# VHFA_RF_detector.net
KiCad netlist of a schematic drawn in Altium Designer
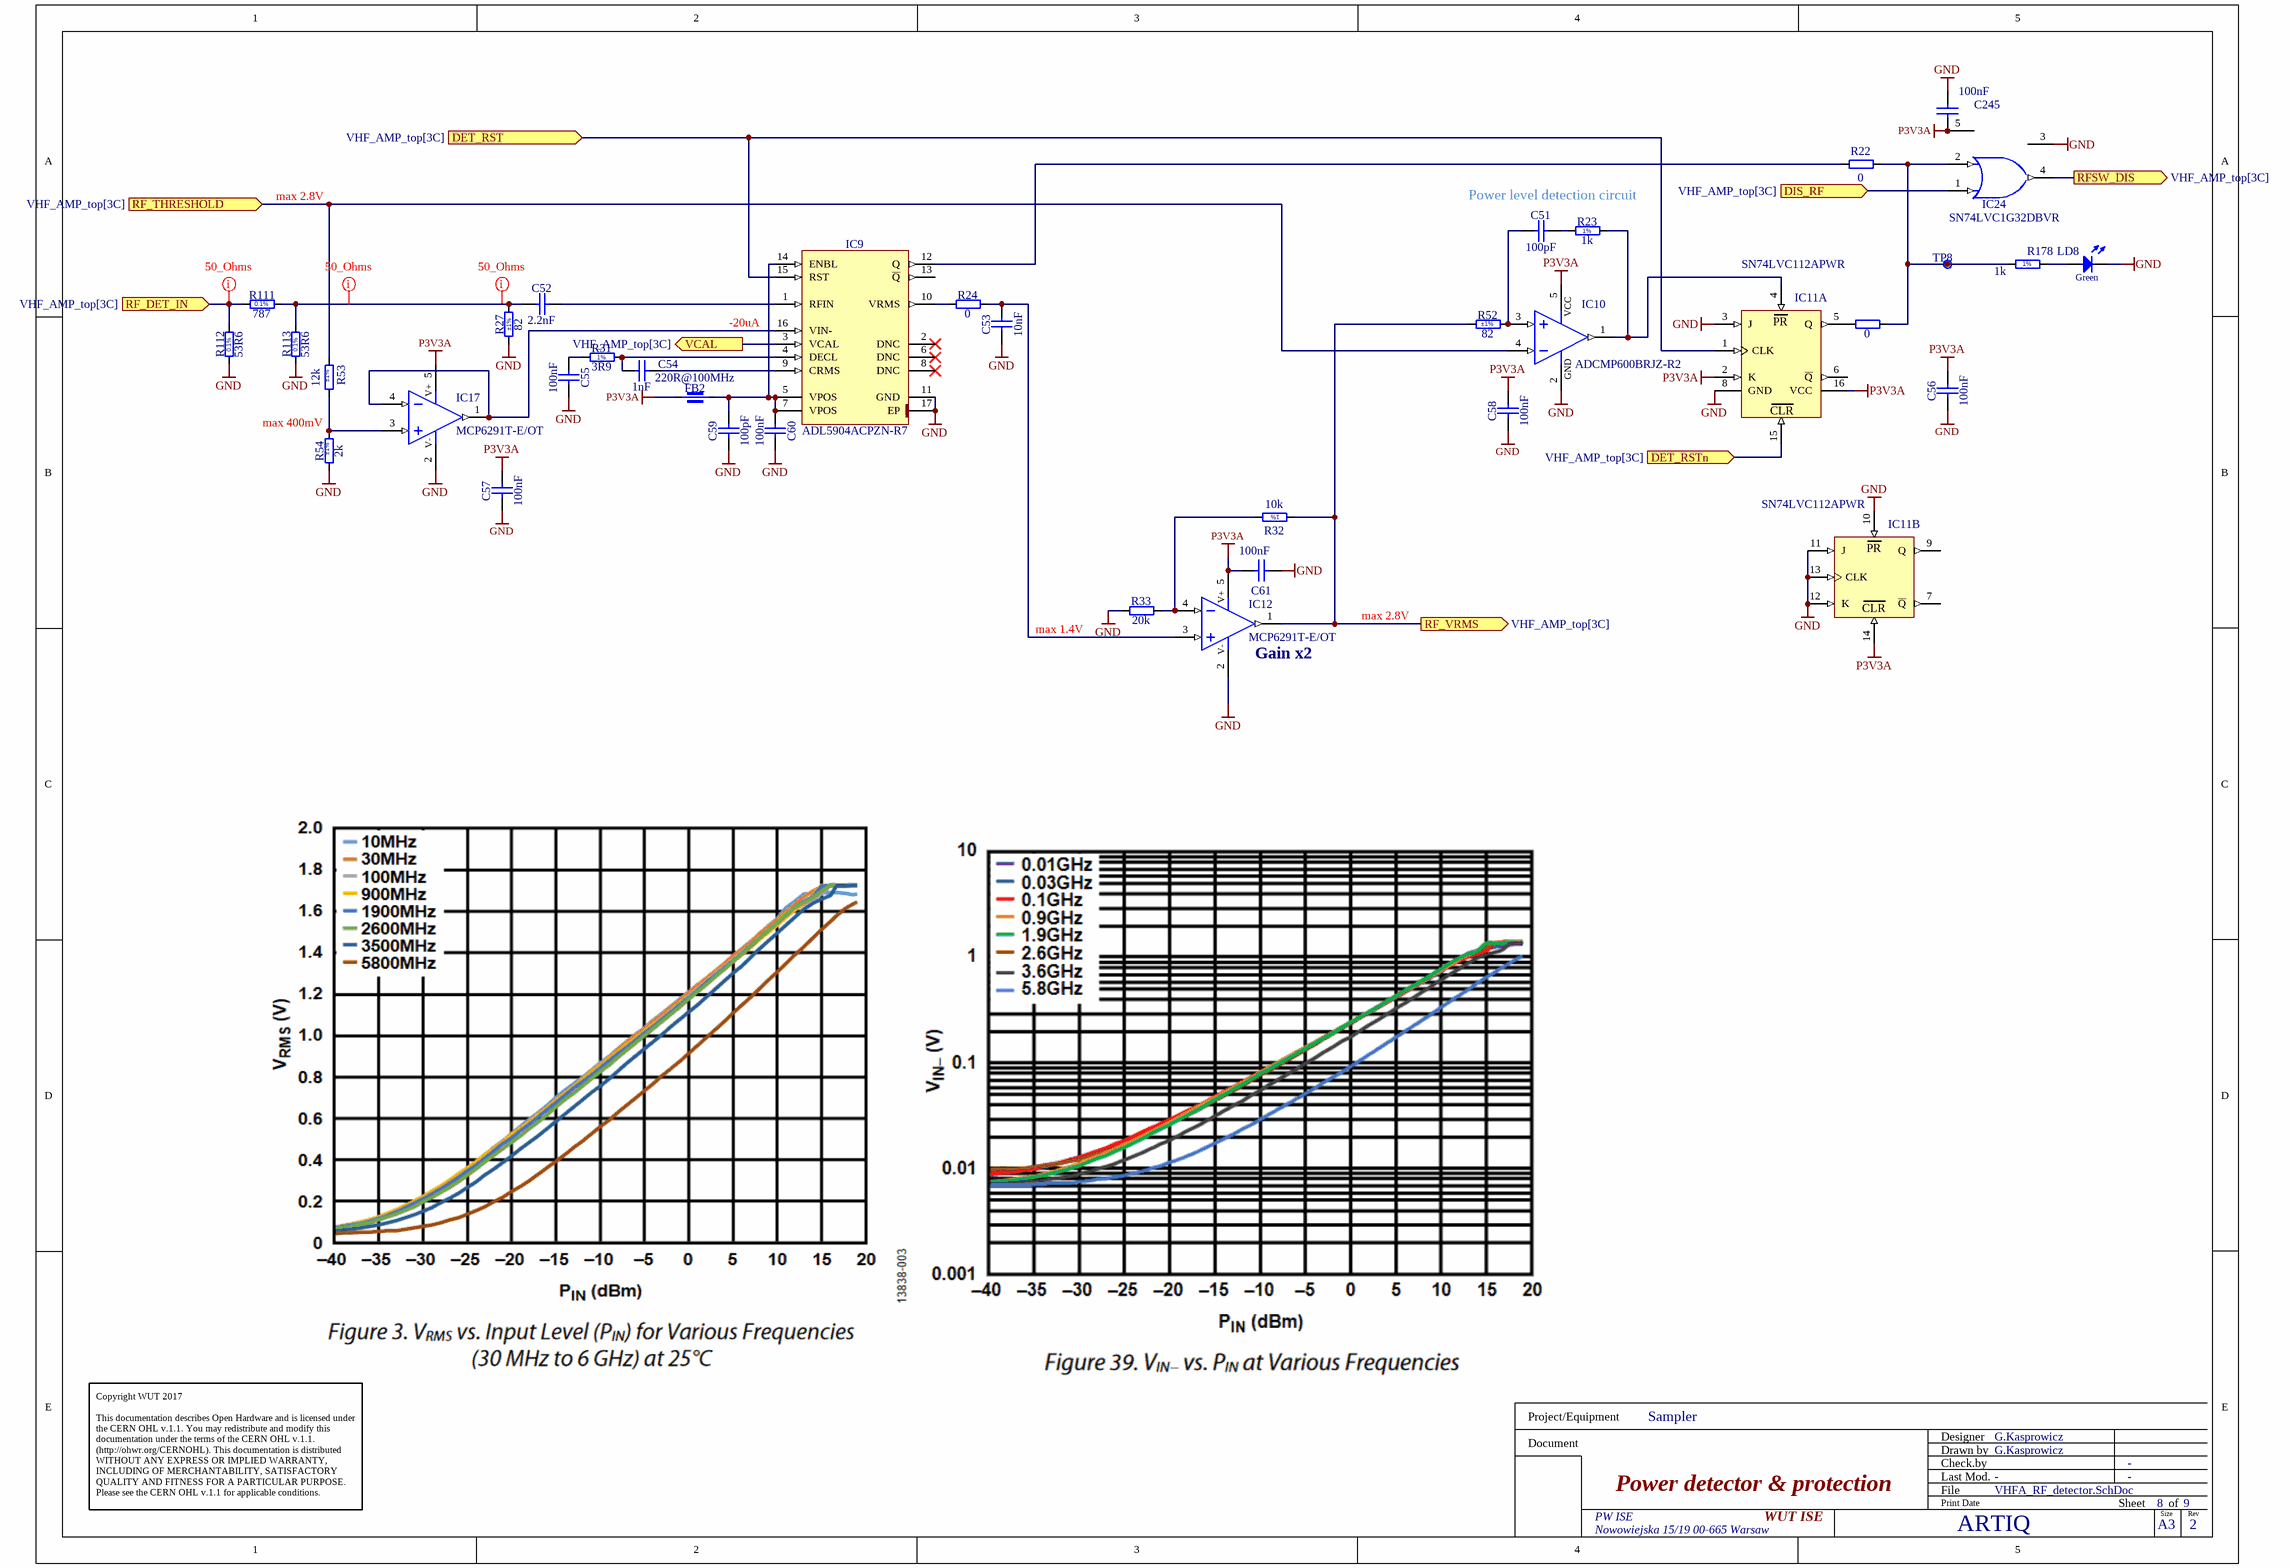
[diagram p0: VHFA_RF_detector.SchDoc]

(export (version "E")
  (design (tool "Eeschema 10.0.6"))
  (components
    (comp (ref "C51")
      (value "100pF")
      (footprint "CAPC1005X55N")
      (description "Non-polarised capacitor")
      (fields
        (field (name "PART NUMBER") "CC0402_100PF_50V_5%_C0G")
        (field (name "VOLTAGE") "50V")
        (field (name "AUTHOR") "CERN DEM JLC")
      )
      (libsource (lib "Capacitors") (part "Capacitor - non polarized"))
    )
    (comp (ref "C52")
      (value "2.2nF")
      (footprint "CAPC1608X87N")
      (description "Non-polarised capacitor")
      (fields
        (field (name "MANUFACTURER") "GENERIC")
        (field (name "MANUFACTURER PART NUMBER") "CC0603_2.2NF_50V_5%_C0G")
        (field (name "AUTHOR") "CERN DEM JMW")
      )
      (libsource (lib "Capacitors") (part "Capacitor - non polarized"))
    )
    (comp (ref "C53")
      (value "10nF")
      (footprint "CAPC1005X55N")
      (description "Non-polarised capacitor")
      (fields
        (field (name "MANUFACTURER") "GENERIC")
        (field (name "MANUFACTURER PART NUMBER") "CC0402_10NF_25V_10%_X7R")
        (field (name "AUTHOR") "CERN DEM JLC")
      )
      (libsource (lib "Capacitors") (part "Capacitor - non polarized"))
    )
    (comp (ref "C54")
      (value "1nF")
      (footprint "CAPC1005X55N")
      (description "Non-polarised capacitor")
      (fields
        (field (name "PART NUMBER") "CC0402_1NF_50V_10%_X7R")
        (field (name "VOLTAGE") "50V")
        (field (name "AUTHOR") "CERN DEM JLC")
      )
      (libsource (lib "Capacitors") (part "Capacitor - non polarized"))
    )
    (comp (ref "C55")
      (value "100nF")
      (footprint "CAPC1005X55N")
      (description "Non-polarised capacitor")
      (fields
        (field (name "MANUFACTURER") "GENERIC")
        (field (name "MANUFACTURER PART NUMBER") "CC0402_100NF_50V_10%_X7R")
        (field (name "AUTHOR") "CERN DEM MR")
      )
      (libsource (lib "Capacitors") (part "Capacitor - non polarized"))
    )
    (comp (ref "C56")
      (value "100nF")
      (footprint "CAPC1005X55N")
      (description "Non-polarised capacitor")
      (fields
        (field (name "PART NUMBER") "CC0402_100NF_16V_10%_X5R")
        (field (name "VOLTAGE") "16V")
        (field (name "AUTHOR") "CERN DEM JLC")
      )
      (libsource (lib "Capacitors") (part "Capacitor - non polarized"))
    )
    (comp (ref "C57")
      (value "100nF")
      (footprint "CAPC1005X55N")
      (description "Non-polarised capacitor")
      (fields
        (field (name "PART NUMBER") "CC0402_100NF_16V_10%_X5R")
        (field (name "VOLTAGE") "16V")
        (field (name "AUTHOR") "CERN DEM JLC")
      )
      (libsource (lib "Capacitors") (part "Capacitor - non polarized"))
    )
    (comp (ref "C58")
      (value "100nF")
      (footprint "CAPC1005X55N")
      (description "Non-polarised capacitor")
      (fields
        (field (name "PART NUMBER") "CC0402_100NF_16V_10%_X5R")
        (field (name "VOLTAGE") "16V")
        (field (name "AUTHOR") "CERN DEM JLC")
      )
      (libsource (lib "Capacitors") (part "Capacitor - non polarized"))
    )
    (comp (ref "C59")
      (value "100pF")
      (footprint "CAPC1005X55N")
      (description "Non-polarised capacitor")
      (fields
        (field (name "PART NUMBER") "CC0402_100PF_50V_5%_C0G")
        (field (name "VOLTAGE") "50V")
        (field (name "AUTHOR") "CERN DEM JLC")
      )
      (libsource (lib "Capacitors") (part "Capacitor - non polarized"))
    )
    (comp (ref "C60")
      (value "100nF")
      (footprint "CAPC1005X55N")
      (description "Non-polarised capacitor")
      (fields
        (field (name "MANUFACTURER") "GENERIC")
        (field (name "MANUFACTURER PART NUMBER") "CC0402_100NF_50V_10%_X7R")
        (field (name "AUTHOR") "CERN DEM MR")
      )
      (libsource (lib "Capacitors") (part "Capacitor - non polarized"))
    )
    (comp (ref "C61")
      (value "100nF")
      (footprint "CAPC1005X55N")
      (description "Non-polarised capacitor")
      (fields
        (field (name "MANUFACTURER") "GENERIC")
        (field (name "MANUFACTURER PART NUMBER") "CC0402_100NF_16V_10%_X5R")
        (field (name "AUTHOR") "CERN DEM JLC")
      )
      (libsource (lib "Capacitors") (part "Capacitor - non polarized"))
    )
    (comp (ref "C245")
      (value "100nF")
      (footprint "CAPC1005X55N")
      (description "Non-polarised capacitor")
      (fields
        (field (name "PART NUMBER") "CC0402_100NF_16V_10%_X5R")
        (field (name "VOLTAGE") "16V")
        (field (name "AUTHOR") "CERN DEM JLC")
      )
      (libsource (lib "Capacitors") (part "Capacitor - non polarized"))
    )
    (comp (ref "FB2")
      (value "220R@100MHz")
      (footprint "INDC1005X55N")
      (fields
        (field (name "PART NUMBER") "IND0402_MURATA_BLM15HB221SN1")
        (field (name "POWER") "250mA")
        (field (name "TOLERANCE") "±25%")
        (field (name "AUTHOR") "CERN DEM JLC")
      )
      (libsource (lib "Inductors & Transformers") (part "Ferrite Bead"))
    )
    (comp (ref "IC9")
      (value "ADL5904ACPZN-R7")
      (footprint "QFN50P300X300X80-17N-S175")
      (description "DC to 6 GHz, 45 dB TruPwr Detector With Envelope Threshold Detection")
      (fields (field (name "MANUFACTURER") "ANALOG DEVICES") (field (name "AUTHOR") "CERN DEM MR"))
      (libsource (lib "ICs And Semiconductors") (part "ADL5904"))
    )
    (comp (ref "IC10")
      (value "ADCMP600BRJZ-R2")
      (footprint "SOT95P280X145-5N")
      (description "Rail-to-Rail, Very Fast, 2.5 V to 5.5 V Single-Supply TTL/CMOS Comparator")
      (fields (field (name "MANUFACTURER") "ANALOG DEVICES") (field (name "AUTHOR") "CERN DEM JLC"))
      (libsource (lib "ICs And Semiconductors") (part "ADCMP600"))
    )
    (comp (ref "IC11")
      (value "SN74LVC112APWR")
      (footprint "SOP65P640X120-16N")
      (description "Dual Negative-Edge-Triggered J-K Flip-Flop With Clear And Preset")
      (fields (field (name "MANUFACTURER") "TEXAS INSTRUMENTS") (field (name "AUTHOR") "CERN DEM JLC"))
      (libsource (lib "ICS-logic") (part "74LVC112APWR"))
    )
    (comp (ref "IC12")
      (value "MCP6291T-E/OT")
      (footprint "SOT95P270X145-5N")
      (description "Operational Amplifier")
      (fields (field (name "MANUFACTURER") "MICROCHIP TECHNOLOGY") (field (name "AUTHOR") "CERN DEM BC"))
      (libsource (lib "ICs And Semiconductors") (part "Operational Amplifier Type7"))
    )
    (comp (ref "IC17")
      (value "MCP6291T-E/OT")
      (footprint "SOT95P270X145-5N")
      (description "Operational Amplifier")
      (fields (field (name "MANUFACTURER") "MICROCHIP TECHNOLOGY") (field (name "AUTHOR") "CERN DEM BC"))
      (libsource (lib "ICs And Semiconductors") (part "Operational Amplifier Type7"))
    )
    (comp (ref "IC24")
      (value "SN74LVC1G32DBVR")
      (footprint "SOT95P280X145-5N")
      (description "Single 2-Input Positive-OR Gate")
      (fields (field (name "MANUFACTURER") "TEXAS INSTRUMENTS") (field (name "AUTHOR") "CERN DEM JLC"))
      (libsource (lib "ICs And Semiconductors") (part "741G32"))
    )
    (comp (ref "LD8")
      (value "Green")
      (footprint "LED_KINGBRIGHT_KPH-1608CGCK")
      (description "LED Green 1C 2A")
      (fields
        (field (name "PART NUMBER") "LED_KINGBRIGHT_KPH-1608CGCK")
        (field (name "MANUFACTURER") "KINGBRIGHT")
        (field (name "AUTHOR") "CERN DEM JLC")
      )
      (libsource (lib "ICs And Semiconductors") (part "LED Green 1C 2A"))
    )
    (comp (ref "R22")
      (value "0")
      (footprint "RESC1608X55N")
      (description "Resistor")
      (fields
        (field (name "PART NUMBER") "R0603_0R_JUMPER")
        (field (name "MANUFACTURER") "GENERIC")
        (field (name "AUTHOR") "CERN DEM JLC")
      )
      (libsource (lib "Resistors") (part "Resistor"))
    )
    (comp (ref "R23")
      (value "1k")
      (footprint "RESC1005X40N")
      (description "Resistor - 1%")
      (fields
        (field (name "PART NUMBER") "R0402_1K_1%_0.0625W_100PPM")
        (field (name "POWER") "0.0625W")
        (field (name "AUTHOR") "CERN DEM JLC")
      )
      (libsource (lib "Resistors") (part "Resistor - 1%"))
    )
    (comp (ref "R24")
      (value "0")
      (footprint "RESC1005X40N")
      (description "Resistor")
      (fields
        (field (name "MANUFACTURER") "GENERIC")
        (field (name "MANUFACTURER PART NUMBER") "R0402_0R_JUMPER")
        (field (name "AUTHOR") "CERN DEM JLC")
      )
      (libsource (lib "Resistors") (part "Resistor"))
    )
    (comp (ref "R25")
      (value "0")
      (footprint "RESC1608X55N")
      (description "Resistor")
      (fields
        (field (name "PART NUMBER") "R0603_0R_JUMPER")
        (field (name "MANUFACTURER") "GENERIC")
        (field (name "AUTHOR") "CERN DEM JLC")
      )
      (libsource (lib "Resistors") (part "Resistor"))
    )
    (comp (ref "R27")
      (value "82")
      (footprint "RESC1608X55N")
      (description "Resistor - 1%")
      (fields
        (field (name "TOLERANCE") "±1%")
        (field (name "PART NUMBER") "R0603_82R_1%_0.1W_100PPM")
        (field (name "POWER") "0.1W")
        (field (name "AUTHOR") "CERN DEM JLC")
      )
      (libsource (lib "Resistors") (part "Resistor - 1%"))
    )
    (comp (ref "R31")
      (value "3R9")
      (footprint "RESC1005X40N")
      (description "Resistor - 1%")
      (fields
        (field (name "PART NUMBER") "R0402_3R9_1%_0.0625W_200PPM")
        (field (name "POWER") "0.0625W")
        (field (name "AUTHOR") "CERN DEM JLC")
      )
      (libsource (lib "Resistors") (part "Resistor - 1%"))
    )
    (comp (ref "R32")
      (value "10k")
      (footprint "RESC1005X40N")
      (description "Resistor - 1%")
      (fields
        (field (name "MANUFACTURER") "GENERIC")
        (field (name "MANUFACTURER PART NUMBER") "R0402_10K_1%_0.0625W_100PPM")
        (field (name "AUTHOR") "CERN DEM JLC")
      )
      (libsource (lib "Resistors") (part "Resistor - 1%"))
    )
    (comp (ref "R33")
      (value "20k")
      (footprint "RESC1005X40N")
      (description "Resistor - 1%")
      (fields
        (field (name "PART NUMBER") "R0402_20K_1%_0.0625W_100PPM")
        (field (name "POWER") "0.0625W")
        (field (name "AUTHOR") "CERN DEM JLC")
      )
      (libsource (lib "Resistors") (part "Resistor - 1%"))
    )
    (comp (ref "R52")
      (value "82")
      (footprint "RESC1005X40N")
      (description "Resistor - 1%")
      (fields
        (field (name "TOLERANCE") "±1%")
        (field (name "PART NUMBER") "R0402_82R_1%_0.0625W_100PPM")
        (field (name "POWER") "0.0625W")
        (field (name "AUTHOR") "CERN DEM JLC")
      )
      (libsource (lib "Resistors") (part "Resistor - 1%"))
    )
    (comp (ref "R53")
      (value "12k")
      (footprint "RESC1005X40N")
      (description "Resistor - 1%")
      (fields
        (field (name "MANUFACTURER") "GENERIC")
        (field (name "MANUFACTURER PART NUMBER") "R0402_12K_1%_0.0625W_100PPM")
        (field (name "TOLERANCE") "±1%")
        (field (name "AUTHOR") "CERN DEM JLC")
      )
      (libsource (lib "Resistors") (part "Resistor - 1%"))
    )
    (comp (ref "R54")
      (value "2k")
      (footprint "RESC1005X40N")
      (description "Resistor - 1%")
      (fields
        (field (name "PART NUMBER") "R0402_2K_1%_0.0625W_100PPM")
        (field (name "POWER") "0.0625W")
        (field (name "TOLERANCE") "±1%")
        (field (name "AUTHOR") "CERN DEM JLC")
      )
      (libsource (lib "Resistors") (part "Resistor - 1%"))
    )
    (comp (ref "R111")
      (value "787")
      (footprint "RESC2012X60N")
      (description "Resistor - 0.1%")
      (fields
        (field (name "PART NUMBER") "R0805_787R_0.1%_0.1W_10PPM")
        (field (name "POWER") "0.1W")
        (field (name "AUTHOR") "CERN DEM JLC")
      )
      (libsource (lib "Resistors") (part "Resistor - 0.1%"))
    )
    (comp (ref "R112")
      (value "53R6")
      (footprint "RESC2012X60N")
      (description "Resistor - 0.1%")
      (fields
        (field (name "PART NUMBER") "R0805_53R6_0.1%_0.1W_10PPM")
        (field (name "POWER") "0.1W")
        (field (name "AUTHOR") "CERN DEM JLC")
      )
      (libsource (lib "Resistors") (part "Resistor - 0.1%"))
    )
    (comp (ref "R113")
      (value "53R6")
      (footprint "RESC2012X60N")
      (description "Resistor - 0.1%")
      (fields
        (field (name "PART NUMBER") "R0805_53R6_0.1%_0.1W_10PPM")
        (field (name "POWER") "0.1W")
        (field (name "AUTHOR") "CERN DEM JLC")
      )
      (libsource (lib "Resistors") (part "Resistor - 0.1%"))
    )
    (comp (ref "R178")
      (value "1k")
      (footprint "RESC1608X55N")
      (description "Resistor - 1%")
      (fields
        (field (name "MANUFACTURER") "GENERIC")
        (field (name "MANUFACTURER PART NUMBER") "R0603_1K_1%_0.1W_100PPM")
        (field (name "AUTHOR") "CERN DEM JLC")
      )
      (libsource (lib "") (part "Resistor - 1%_1"))
    )
    (comp (ref "TP8")
      (value "Test Point")
      (footprint "TPS127")
      (fields (field (name "PART NUMBER") "SMD_PAD_1.27X1.27MM") (field (name "AUTHOR") "CERN DEM JLC"))
      (libsource (lib "Eletro-mechanical") (part "Test Point"))
    )
  )
  (nets
    (net (code "1") (name "/DET_RST") (class "Default")
      (node (ref "IC11") (pin "1") (pinfunction "CLK_1") (pintype "input"))
      (node (ref "IC9") (pin "15") (pinfunction "RST_15") (pintype "input"))
    )
    (net (code "2") (name "/DET_RSTn") (class "Default")
      (node (ref "IC11") (pin "15") (pinfunction "~{CLR}_15") (pintype "input"))
    )
    (net (code "3") (name "/DIS_RF") (class "Default")
      (node (ref "IC24") (pin "1") (pinfunction "A_1") (pintype "input"))
    )
    (net (code "4") (name "/RFSW_DIS") (class "Default")
      (node (ref "IC24") (pin "4") (pinfunction "Y_4") (pintype "output"))
    )
    (net (code "5") (name "/RF_DET_IN") (class "Default")
      (node (ref "R111") (pin "1") (pinfunction "1_1") (pintype "passive"))
      (node (ref "R112") (pin "2") (pinfunction "2_2") (pintype "passive"))
    )
    (net (code "6") (name "/RF_THRESHOLD") (class "Default")
      (node (ref "IC10") (pin "4") (pinfunction "VN_4") (pintype "input"))
      (node (ref "R53") (pin "1") (pinfunction "1_1") (pintype "passive"))
    )
    (net (code "7") (name "/RF_VRMS") (class "Default")
      (node (ref "IC12") (pin "1") (pinfunction "OUT_1") (pintype "output"))
      (node (ref "R32") (pin "1") (pinfunction "1_1") (pintype "passive"))
      (node (ref "R52") (pin "1") (pinfunction "1_1") (pintype "passive"))
    )
    (net (code "8") (name "/VCAL") (class "Default")
      (node (ref "IC9") (pin "3") (pinfunction "VCAL_3") (pintype "input"))
    )
    (net (code "9") (name "GND") (class "Default")
      (node (ref "C245") (pin "2") (pinfunction "2_2") (pintype "passive"))
      (node (ref "C53") (pin "1") (pinfunction "1_1") (pintype "passive"))
      (node (ref "C55") (pin "2") (pinfunction "2_2") (pintype "passive"))
      (node (ref "C56") (pin "1") (pinfunction "1_1") (pintype "passive"))
      (node (ref "C57") (pin "1") (pinfunction "1_1") (pintype "passive"))
      (node (ref "C58") (pin "1") (pinfunction "1_1") (pintype "passive"))
      (node (ref "C59") (pin "1") (pinfunction "1_1") (pintype "passive"))
      (node (ref "C60") (pin "2") (pinfunction "2_2") (pintype "passive"))
      (node (ref "C61") (pin "1") (pinfunction "1_1") (pintype "passive"))
      (node (ref "IC10") (pin "2") (pinfunction "GND_2") (pintype "power_in"))
      (node (ref "IC11") (pin "10") (pinfunction "~{PRE}_10") (pintype "input"))
      (node (ref "IC11") (pin "11") (pinfunction "J_11") (pintype "input"))
      (node (ref "IC11") (pin "12") (pinfunction "K_12") (pintype "input"))
      (node (ref "IC11") (pin "13") (pinfunction "CLK_13") (pintype "input"))
      (node (ref "IC11") (pin "3") (pinfunction "J_3") (pintype "input"))
      (node (ref "IC11") (pin "8") (pinfunction "GND_8") (pintype "power_in"))
      (node (ref "IC12") (pin "2") (pinfunction "V-_2") (pintype "power_in"))
      (node (ref "IC17") (pin "2") (pinfunction "V-_2") (pintype "power_in"))
      (node (ref "IC24") (pin "3") (pinfunction "GND_3") (pintype "power_in"))
      (node (ref "IC9") (pin "11") (pinfunction "GND_11") (pintype "power_in"))
      (node (ref "IC9") (pin "17") (pinfunction "EP_17") (pintype "power_in"))
      (node (ref "LD8") (pin "1") (pinfunction "C_1") (pintype "passive"))
      (node (ref "R112") (pin "1") (pinfunction "1_1") (pintype "passive"))
      (node (ref "R113") (pin "1") (pinfunction "1_1") (pintype "passive"))
      (node (ref "R27") (pin "1") (pinfunction "1_1") (pintype "passive"))
      (node (ref "R33") (pin "1") (pinfunction "1_1") (pintype "passive"))
      (node (ref "R54") (pin "1") (pinfunction "1_1") (pintype "passive"))
    )
    (net (code "10") (name "Net-(C51-Pad2)") (class "Default")
      (node (ref "C51") (pin "2") (pinfunction "2_2") (pintype "passive"))
      (node (ref "R23") (pin "1") (pinfunction "1_1") (pintype "passive"))
    )
    (net (code "11") (name "Net-(C52-Pad1)") (class "Default")
      (node (ref "C52") (pin "1") (pinfunction "1_1") (pintype "passive"))
      (node (ref "R111") (pin "2") (pinfunction "2_2") (pintype "passive"))
      (node (ref "R113") (pin "2") (pinfunction "2_2") (pintype "passive"))
      (node (ref "R27") (pin "2") (pinfunction "2_2") (pintype "passive"))
    )
    (net (code "12") (name "Net-(C55-Pad1)") (class "Default")
      (node (ref "C55") (pin "1") (pinfunction "1_1") (pintype "passive"))
      (node (ref "R31") (pin "1") (pinfunction "1_1") (pintype "passive"))
    )
    (net (code "13") (name "Net-(IC9-CRMS)") (class "Default")
      (node (ref "C54") (pin "2") (pinfunction "2_2") (pintype "passive"))
      (node (ref "IC9") (pin "9") (pinfunction "CRMS_9") (pintype "input"))
    )
    (net (code "14") (name "Net-(IC9-DECL)") (class "Default")
      (node (ref "C54") (pin "1") (pinfunction "1_1") (pintype "passive"))
      (node (ref "IC9") (pin "4") (pinfunction "DECL_4") (pintype "input"))
      (node (ref "R31") (pin "2") (pinfunction "2_2") (pintype "passive"))
    )
    (net (code "15") (name "Net-(IC9-ENBL)") (class "Default")
      (node (ref "C59") (pin "2") (pinfunction "2_2") (pintype "passive"))
      (node (ref "C60") (pin "1") (pinfunction "1_1") (pintype "passive"))
      (node (ref "FB2") (pin "2") (pinfunction "2_2") (pintype "passive"))
      (node (ref "IC9") (pin "14") (pinfunction "ENBL_14") (pintype "input"))
      (node (ref "IC9") (pin "5") (pinfunction "VPOS_5") (pintype "power_in"))
      (node (ref "IC9") (pin "7") (pinfunction "VPOS_7") (pintype "power_in"))
    )
    (net (code "16") (name "Net-(IC9-Q)") (class "Default")
      (node (ref "IC9") (pin "12") (pinfunction "Q_12") (pintype "output"))
      (node (ref "R22") (pin "1") (pinfunction "1_1") (pintype "passive"))
    )
    (net (code "17") (name "Net-(IC9-RFIN)") (class "Default")
      (node (ref "C52") (pin "2") (pinfunction "2_2") (pintype "passive"))
      (node (ref "IC9") (pin "1") (pinfunction "RFIN_1") (pintype "input"))
    )
    (net (code "18") (name "Net-(IC9-VRMS)") (class "Default")
      (node (ref "IC9") (pin "10") (pinfunction "VRMS_10") (pintype "output"))
      (node (ref "R24") (pin "1") (pinfunction "1_1") (pintype "passive"))
    )
    (net (code "19") (name "Net-(IC10-VP)") (class "Default")
      (node (ref "C51") (pin "1") (pinfunction "1_1") (pintype "passive"))
      (node (ref "IC10") (pin "3") (pinfunction "VP_3") (pintype "input"))
      (node (ref "R52") (pin "2") (pinfunction "2_2") (pintype "passive"))
    )
    (net (code "20") (name "Net-(IC10-q)") (class "Default")
      (node (ref "IC10") (pin "1") (pinfunction "q_1") (pintype "output"))
      (node (ref "IC11") (pin "4") (pinfunction "~{PRE}_4") (pintype "input"))
      (node (ref "R23") (pin "2") (pinfunction "2_2") (pintype "passive"))
    )
    (net (code "21") (name "Net-(IC11A-Q)") (class "Default")
      (node (ref "IC11") (pin "5") (pinfunction "Q_5") (pintype "output"))
      (node (ref "R25") (pin "1") (pinfunction "1_1") (pintype "passive"))
    )
    (net (code "22") (name "Net-(IC12-IN+)") (class "Default")
      (node (ref "C53") (pin "2") (pinfunction "2_2") (pintype "passive"))
      (node (ref "IC12") (pin "3") (pinfunction "IN+_3") (pintype "input"))
      (node (ref "R24") (pin "2") (pinfunction "2_2") (pintype "passive"))
    )
    (net (code "23") (name "Net-(IC12-IN-)") (class "Default")
      (node (ref "IC12") (pin "4") (pinfunction "IN-_4") (pintype "input"))
      (node (ref "R32") (pin "2") (pinfunction "2_2") (pintype "passive"))
      (node (ref "R33") (pin "2") (pinfunction "2_2") (pintype "passive"))
    )
    (net (code "24") (name "Net-(IC17-IN+)") (class "Default")
      (node (ref "IC17") (pin "3") (pinfunction "IN+_3") (pintype "input"))
      (node (ref "R53") (pin "2") (pinfunction "2_2") (pintype "passive"))
      (node (ref "R54") (pin "2") (pinfunction "2_2") (pintype "passive"))
    )
    (net (code "25") (name "Net-(IC17-IN-)") (class "Default")
      (node (ref "IC17") (pin "1") (pinfunction "OUT_1") (pintype "output"))
      (node (ref "IC17") (pin "4") (pinfunction "IN-_4") (pintype "input"))
      (node (ref "IC9") (pin "16") (pinfunction "VIN-_16") (pintype "input"))
    )
    (net (code "26") (name "Net-(IC24-B)") (class "Default")
      (node (ref "IC24") (pin "2") (pinfunction "B_2") (pintype "input"))
      (node (ref "R178") (pin "1") (pinfunction "1_1") (pintype "passive"))
      (node (ref "R22") (pin "2") (pinfunction "2_2") (pintype "passive"))
      (node (ref "R25") (pin "2") (pinfunction "2_2") (pintype "passive"))
      (node (ref "TP8") (pin "1") (pinfunction "1_1") (pintype "bidirectional"))
    )
    (net (code "27") (name "Net-(LD8-A)") (class "Default")
      (node (ref "LD8") (pin "2") (pinfunction "A_2") (pintype "passive"))
      (node (ref "R178") (pin "2") (pinfunction "2_2") (pintype "passive"))
    )
    (net (code "28") (name "P3V3A") (class "Default")
      (node (ref "C245") (pin "1") (pinfunction "1_1") (pintype "passive"))
      (node (ref "C56") (pin "2") (pinfunction "2_2") (pintype "passive"))
      (node (ref "C57") (pin "2") (pinfunction "2_2") (pintype "passive"))
      (node (ref "C58") (pin "2") (pinfunction "2_2") (pintype "passive"))
      (node (ref "C61") (pin "2") (pinfunction "2_2") (pintype "passive"))
      (node (ref "FB2") (pin "1") (pinfunction "1_1") (pintype "passive"))
      (node (ref "IC10") (pin "5") (pinfunction "VCC_5") (pintype "power_in"))
      (node (ref "IC11") (pin "14") (pinfunction "~{CLR}_14") (pintype "input"))
      (node (ref "IC11") (pin "16") (pinfunction "VCC_16") (pintype "power_in"))
      (node (ref "IC11") (pin "2") (pinfunction "K_2") (pintype "input"))
      (node (ref "IC12") (pin "5") (pinfunction "V+_5") (pintype "power_in"))
      (node (ref "IC17") (pin "5") (pinfunction "V+_5") (pintype "power_in"))
      (node (ref "IC24") (pin "5") (pinfunction "VCC_5") (pintype "power_in"))
    )
    (net (code "29") (name "unconnected-(IC9-DNC-Pad2)") (class "Default")
      (node (ref "IC9") (pin "2") (pinfunction "DNC_2") (pintype "passive+no_connect"))
    )
    (net (code "30") (name "unconnected-(IC9-DNC-Pad6)") (class "Default")
      (node (ref "IC9") (pin "6") (pinfunction "DNC_6") (pintype "passive+no_connect"))
    )
    (net (code "31") (name "unconnected-(IC9-DNC-Pad8)") (class "Default")
      (node (ref "IC9") (pin "8") (pinfunction "DNC_8") (pintype "passive+no_connect"))
    )
    (net (code "32") (name "unconnected-(IC9-~{Q}-Pad13)") (class "Default")
      (node (ref "IC9") (pin "13") (pinfunction "~{Q}_13") (pintype "output"))
    )
    (net (code "33") (name "unconnected-(IC11A-~{Q}-Pad6)") (class "Default")
      (node (ref "IC11") (pin "6") (pinfunction "~{Q}_6") (pintype "output"))
    )
    (net (code "34") (name "unconnected-(IC11B-Q-Pad9)") (class "Default")
      (node (ref "IC11") (pin "9") (pinfunction "Q_9") (pintype "output"))
    )
    (net (code "35") (name "unconnected-(IC11B-~{Q}-Pad7)") (class "Default")
      (node (ref "IC11") (pin "7") (pinfunction "~{Q}_7") (pintype "output"))
    )
  )
)
